# just_a_switch-mk-2_1.net
KiCad netlist of a schematic drawn in EAGLE
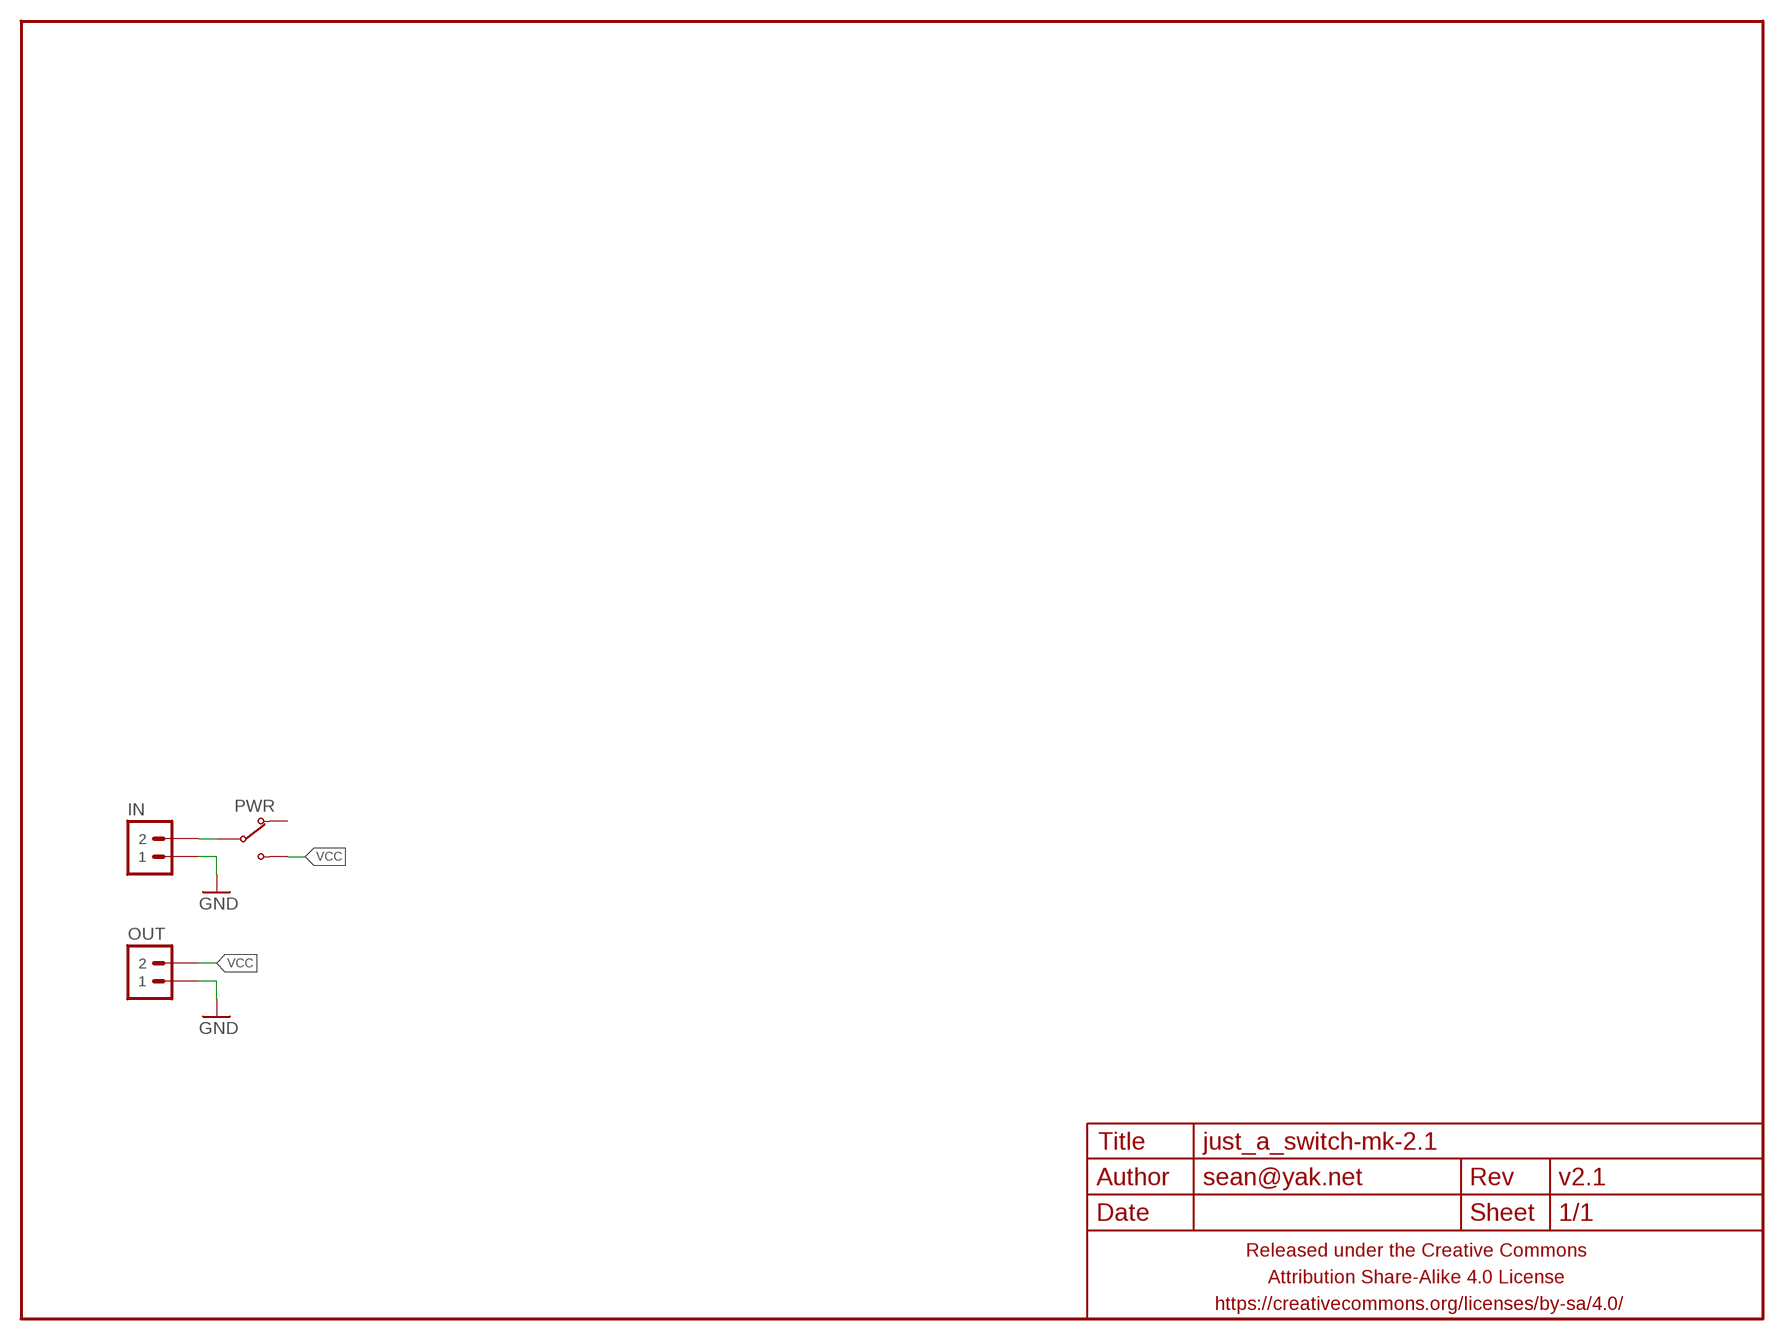
[diagram p0: schematic, sheet 1]

(export (version "E")
  (design (tool "Eeschema 10.0.6"))
  (components
    (comp (ref "FRAME1")
      (value "FRAME-LETTERNO_PACKAGE")
      (footprint "eagle-import:DUMMY")
      (fields (field (name "DESIGNER") "sean@yak.net") (field (name "VERSION") "v2.1"))
      (libsource (lib "eagle-import") (part "FRAME-LETTERNO_PACKAGE"))
    )
    (comp (ref "IN")
      (value "M02JST-PH-VERT-R+")
      (footprint "eagle-import:JST-2-PH-VERT-PTH-R+")
      (libsource (lib "eagle-import") (part "M02JST-PH-VERT-R+"))
    )
    (comp (ref "OUT")
      (value "M02JST-PH-VERT-R+")
      (footprint "eagle-import:JST-2-PH-VERT-PTH-R+")
      (libsource (lib "eagle-import") (part "M02JST-PH-VERT-R+"))
    )
    (comp (ref "PWR")
      (value "SWITCH-SPDTPTH-RA-2.54MM")
      (footprint "eagle-import:SPDT-RA-2.54MM")
      (libsource (lib "eagle-import") (part "SWITCH-SPDTPTH-RA-2.54MM"))
    )
  )
  (nets
    (net (code "1") (name "GND") (class "Default")
      (node (ref "IN") (pin "1") (pinfunction "1_1") (pintype "passive"))
      (node (ref "OUT") (pin "1") (pinfunction "1_1") (pintype "passive"))
    )
    (net (code "2") (name "Net-(PWR-COM)") (class "Default")
      (node (ref "IN") (pin "2") (pinfunction "2_2") (pintype "passive"))
      (node (ref "PWR") (pin "2") (pinfunction "COM_2") (pintype "passive"))
    )
    (net (code "3") (name "VCC") (class "Default")
      (node (ref "OUT") (pin "2") (pinfunction "2_2") (pintype "passive"))
      (node (ref "PWR") (pin "3") (pinfunction "NO_3") (pintype "passive"))
    )
    (net (code "4") (name "unconnected-(PWR-NC-Pad1)") (class "Default")
      (node (ref "PWR") (pin "1") (pinfunction "NC_1") (pintype "passive"))
    )
  )
)
